# 08-Power.net
KiCad netlist of a schematic drawn in Altium Designer
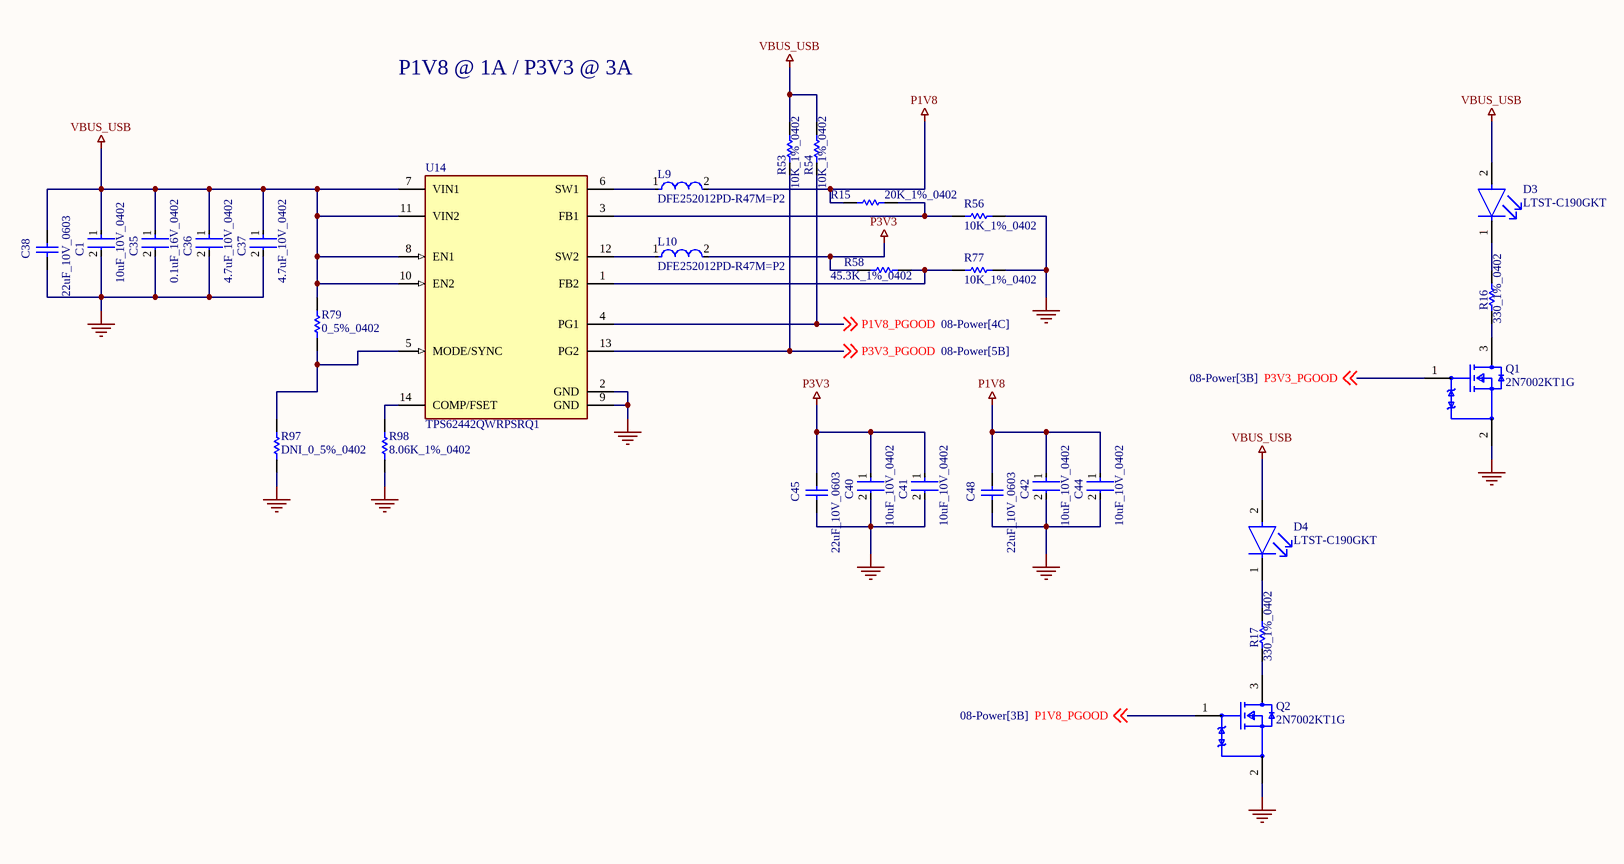
[diagram p0: 08-Power.SchDoc]

(export (version "E")
  (design (tool "Eeschema 10.0.6"))
  (components
    (comp (ref "C1")
      (value "10uF_10V_0402")
      (footprint "FP-CL05A106MP5NUNC-MFG")
      (description "CAP CER 10UF 10V X5R 0402")
      (fields
        (field (name "OCTOPART") "https://octopart.com/cl05a106mp5nunc-samsung-22457395")
        (field (name "TOLERANCE") "20%")
      )
      (libsource (lib "Altium Content Vault") (part "b4654b650e69147ec39a6b967a45e02"))
    )
    (comp (ref "C35")
      (value "0.1uF_16V_0402")
      (footprint "FP-C0402-BB-MFG")
      (description "CAP CER 0.1UF 16V 5% X7R 0402")
      (fields
        (field (name "MANUFACTURER") "Kemet")
        (field (name "MANUFACTURER PART NUMBER") "C0402C104J4RACTU")
      )
      (libsource (lib "Altium Content Vault") (part "b4654b650e69147ec39a6b967a45e02"))
    )
    (comp (ref "C36")
      (value "4.7uF_10V_0402")
      (footprint "FP-C1005-050-0_15-MFG")
      (description "CAP CER 4.7UF 10V X5R 0402")
      (fields (field (name "TOLERANCE") "10%"))
      (libsource (lib "Altium Content Vault") (part "b4654b650e69147ec39a6b967a45e02"))
    )
    (comp (ref "C37")
      (value "4.7uF_10V_0402")
      (footprint "FP-C1005-050-0_15-MFG")
      (description "CAP CER 4.7UF 10V X5R 0402")
      (fields (field (name "TOLERANCE") "10%"))
      (libsource (lib "Altium Content Vault") (part "b4654b650e69147ec39a6b967a45e02"))
    )
    (comp (ref "C38")
      (value "22uF_10V_0603")
      (footprint "CAPC1608X100X20ML10")
      (description "Chip Capacitor, 22 uF, +/- 20%, 10 V, -55 to 85 degC, 0603 (1608 Metric), RoHS, Tape and Reel")
      (fields (field (name "MANUFACTURER") "TDK") (field (name "TOLERANCE") "±20%"))
      (libsource (lib "Altium Content Vault") (part "CAP-NP-2"))
    )
    (comp (ref "C40")
      (value "10uF_10V_0402")
      (footprint "FP-CL05A106MP5NUNC-MFG")
      (description "CAP CER 10UF 10V X5R 0402")
      (fields
        (field (name "OCTOPART") "https://octopart.com/cl05a106mp5nunc-samsung-22457395")
        (field (name "TOLERANCE") "20%")
      )
      (libsource (lib "Altium Content Vault") (part "b4654b650e69147ec39a6b967a45e02"))
    )
    (comp (ref "C41")
      (value "10uF_10V_0402")
      (footprint "FP-CL05A106MP5NUNC-MFG")
      (description "CAP CER 10UF 10V X5R 0402")
      (fields
        (field (name "OCTOPART") "https://octopart.com/cl05a106mp5nunc-samsung-22457395")
        (field (name "TOLERANCE") "20%")
      )
      (libsource (lib "Altium Content Vault") (part "b4654b650e69147ec39a6b967a45e02"))
    )
    (comp (ref "C42")
      (value "10uF_10V_0402")
      (footprint "FP-CL05A106MP5NUNC-MFG")
      (description "CAP CER 10UF 10V X5R 0402")
      (fields
        (field (name "OCTOPART") "https://octopart.com/cl05a106mp5nunc-samsung-22457395")
        (field (name "TOLERANCE") "20%")
      )
      (libsource (lib "Altium Content Vault") (part "b4654b650e69147ec39a6b967a45e02"))
    )
    (comp (ref "C44")
      (value "10uF_10V_0402")
      (footprint "FP-CL05A106MP5NUNC-MFG")
      (description "CAP CER 10UF 10V X5R 0402")
      (fields
        (field (name "OCTOPART") "https://octopart.com/cl05a106mp5nunc-samsung-22457395")
        (field (name "TOLERANCE") "20%")
      )
      (libsource (lib "Altium Content Vault") (part "b4654b650e69147ec39a6b967a45e02"))
    )
    (comp (ref "C45")
      (value "22uF_10V_0603")
      (footprint "CAPC1608X100X20ML10")
      (description "Chip Capacitor, 22 uF, +/- 20%, 10 V, -55 to 85 degC, 0603 (1608 Metric), RoHS, Tape and Reel")
      (fields (field (name "MANUFACTURER") "TDK") (field (name "TOLERANCE") "±20%"))
      (libsource (lib "Altium Content Vault") (part "CAP-NP-2"))
    )
    (comp (ref "C48")
      (value "22uF_10V_0603")
      (footprint "CAPC1608X100X20ML10")
      (description "Chip Capacitor, 22 uF, +/- 20%, 10 V, -55 to 85 degC, 0603 (1608 Metric), RoHS, Tape and Reel")
      (fields (field (name "MANUFACTURER") "TDK") (field (name "TOLERANCE") "±20%"))
      (libsource (lib "Altium Content Vault") (part "CAP-NP-2"))
    )
    (comp (ref "D3")
      (value "LTST-C190GKT")
      (footprint "FP-LTST-C190GKT-MFG")
      (description "LED GREEN CLEAR CHIP SMD")
      (fields (field (name "VOLTAGE") "2V"))
      (libsource (lib "Altium Content Vault") (part "8706943c75ba83719d021d2fdc84c58"))
    )
    (comp (ref "D4")
      (value "LTST-C190GKT")
      (footprint "FP-LTST-C190GKT-MFG")
      (description "LED GREEN CLEAR CHIP SMD")
      (fields (field (name "VOLTAGE") "2V"))
      (libsource (lib "Altium Content Vault") (part "8706943c75ba83719d021d2fdc84c58"))
    )
    (comp (ref "L9")
      (value "DFE252012PD-R47M=P2")
      (footprint "FP-DFE252012C-IPC_A")
      (description "Shielded Wirewound Inductor 0.47uH 20% 4000mA 0.027Ω 1008 (2520)")
      (libsource (lib "Altium Content Vault") (part "725321dda6339637d4d059423bc1c3c"))
    )
    (comp (ref "L10")
      (value "DFE252012PD-R47M=P2")
      (footprint "FP-DFE252012C-IPC_A")
      (description "Shielded Wirewound Inductor 0.47uH 20% 4000mA 0.027Ω 1008 (2520)")
      (libsource (lib "Altium Content Vault") (part "725321dda6339637d4d059423bc1c3c"))
    )
    (comp (ref "Q1")
      (value "2N7002KT1G")
      (footprint "FP-318-08-MFG")
      (description "MOSFET N-CH 60V 320MA SOT-23")
      (libsource (lib "Altium Content Vault") (part "3e4cd9f5cc51be7b9a7c969a1e66e82"))
    )
    (comp (ref "Q2")
      (value "2N7002KT1G")
      (footprint "FP-318-08-MFG")
      (description "MOSFET N-CH 60V 320MA SOT-23")
      (libsource (lib "Altium Content Vault") (part "3e4cd9f5cc51be7b9a7c969a1e66e82"))
    )
    (comp (ref "R15")
      (value "20K_1%_0402")
      (footprint "RESC1005X40X25ML10T10")
      (fields
        (field (name "MANUFACTURER") "TE Connectivity / AMP")
        (field (name "PART NUMBER") "CRG0402F20K")
      )
      (libsource (lib "Altium Content Vault") (part "RES"))
    )
    (comp (ref "R16")
      (value "330_1%_0402")
      (footprint "RESC1005X40X25NL10T10")
      (fields (field (name "MANUFACTURER") "Panasonic") (field (name "PART NUMBER") "ERA-2AED331X"))
      (libsource (lib "Altium Content Vault") (part "RES"))
    )
    (comp (ref "R17")
      (value "330_1%_0402")
      (footprint "RESC1005X40X25NL10T10")
      (fields (field (name "MANUFACTURER") "Panasonic") (field (name "PART NUMBER") "ERA-2AED331X"))
      (libsource (lib "Altium Content Vault") (part "RES"))
    )
    (comp (ref "R53")
      (value "10K_1%_0402")
      (footprint "RESC1005X40X25NL10T10")
      (fields (field (name "MANUFACTURER") "Bourns") (field (name "PART NUMBER") "CR0402-FX-1002GLF"))
      (libsource (lib "Altium Content Vault") (part "RES"))
    )
    (comp (ref "R54")
      (value "10K_1%_0402")
      (footprint "RESC1005X40X25NL10T10")
      (fields (field (name "MANUFACTURER") "Bourns") (field (name "PART NUMBER") "CR0402-FX-1002GLF"))
      (libsource (lib "Altium Content Vault") (part "RES"))
    )
    (comp (ref "R56")
      (value "10K_1%_0402")
      (footprint "RESC1005X40X25NL10T10")
      (fields (field (name "MANUFACTURER") "Bourns") (field (name "PART NUMBER") "CR0402-FX-1002GLF"))
      (libsource (lib "Altium Content Vault") (part "RES"))
    )
    (comp (ref "R58")
      (value "45.3K_1%_0402")
      (footprint "RESC0402(1005)_L")
      (description "45K3 0.063W 1% 0402 (1005 Metric)  SMD")
      (fields (field (name "TOLERANCE") "1 %") (field (name "POWER") "0.063 W"))
      (libsource (lib "Altium Content Vault") (part "RES"))
    )
    (comp (ref "R77")
      (value "10K_1%_0402")
      (footprint "RESC1005X40X25NL10T10")
      (fields (field (name "MANUFACTURER") "Bourns") (field (name "PART NUMBER") "CR0402-FX-1002GLF"))
      (libsource (lib "Altium Content Vault") (part "RES"))
    )
    (comp (ref "R79")
      (value "0_5%_0402")
      (footprint "RESC1005X40X25NL05T10")
      (fields (field (name "MANUFACTURER") "Panasonic") (field (name "PART NUMBER") "ERJ-U020R00X"))
      (libsource (lib "Altium Content Vault") (part "RES"))
    )
    (comp (ref "R97")
      (value "DNI_0_5%_0402")
      (footprint "RESC1005X40X25NL05T10")
      (fields (field (name "MANUFACTURER") "Panasonic") (field (name "PART NUMBER") "ERJ-U020R00X"))
      (libsource (lib "Altium Content Vault") (part "RES"))
    )
    (comp (ref "R98")
      (value "8.06K_1%_0402")
      (footprint "RESC1005X40X25ML05T05")
      (description "Chip Resistor, 8.06 KOhm, +/- 1%, 63 mW, -55 to 155 degC, 0402 (1005 Metric), RoHS, Tape and Reel")
      (fields (field (name "PARTNUMBER") "CRCW04028K06FKED") (field (name "TOLERANCE") "1%"))
      (libsource (lib "Altium Content Vault") (part "RES-2"))
    )
    (comp (ref "U14")
      (value "TPS62442QWRPSRQ1")
      (footprint "FP-RQR0014A-MFG")
      (description "Adjustable-Frequency Dual Step-Down Converter, 2.7-6V VIN, 0.6-5.5V 2A VOUT, VQFN-HR14")
      (libsource (lib "Altium Content Vault") (part "72c5b9bb22caeb688b1070b758806aa"))
    )
  )
  (nets
    (net (code "1") (name "GND") (class "Default")
      (node (ref "C1") (pin "2") (pinfunction "2_2") (pintype "passive"))
      (node (ref "C35") (pin "2") (pinfunction "2_2") (pintype "passive"))
      (node (ref "C36") (pin "2") (pinfunction "2_2") (pintype "passive"))
      (node (ref "C37") (pin "2") (pinfunction "2_2") (pintype "passive"))
      (node (ref "C38") (pin "1") (pinfunction "1_1") (pintype "passive"))
      (node (ref "C40") (pin "2") (pinfunction "2_2") (pintype "passive"))
      (node (ref "C41") (pin "2") (pinfunction "2_2") (pintype "passive"))
      (node (ref "C42") (pin "2") (pinfunction "2_2") (pintype "passive"))
      (node (ref "C44") (pin "2") (pinfunction "2_2") (pintype "passive"))
      (node (ref "C45") (pin "1") (pinfunction "1_1") (pintype "passive"))
      (node (ref "C48") (pin "1") (pinfunction "1_1") (pintype "passive"))
      (node (ref "Q1") (pin "2") (pinfunction "Source_2") (pintype "passive"))
      (node (ref "Q2") (pin "2") (pinfunction "Source_2") (pintype "passive"))
      (node (ref "R56") (pin "1") (pinfunction "1_1") (pintype "passive"))
      (node (ref "R77") (pin "1") (pinfunction "1_1") (pintype "passive"))
      (node (ref "R97") (pin "1") (pinfunction "1_1") (pintype "passive"))
      (node (ref "R98") (pin "1") (pinfunction "1_1") (pintype "passive"))
      (node (ref "U14") (pin "2") (pinfunction "GND_2") (pintype "power_in"))
      (node (ref "U14") (pin "9") (pinfunction "GND_9") (pintype "power_in"))
    )
    (net (code "2") (name "Net-(D3-C)") (class "Default")
      (node (ref "D3") (pin "1") (pinfunction "C_1") (pintype "passive"))
      (node (ref "R16") (pin "2") (pinfunction "2_2") (pintype "passive"))
    )
    (net (code "3") (name "Net-(D4-C)") (class "Default")
      (node (ref "D4") (pin "1") (pinfunction "C_1") (pintype "passive"))
      (node (ref "R17") (pin "2") (pinfunction "2_2") (pintype "passive"))
    )
    (net (code "4") (name "Net-(Q1-Drain)") (class "Default")
      (node (ref "Q1") (pin "3") (pinfunction "Drain_3") (pintype "passive"))
      (node (ref "R16") (pin "1") (pinfunction "1_1") (pintype "passive"))
    )
    (net (code "5") (name "Net-(Q2-Drain)") (class "Default")
      (node (ref "Q2") (pin "3") (pinfunction "Drain_3") (pintype "passive"))
      (node (ref "R17") (pin "1") (pinfunction "1_1") (pintype "passive"))
    )
    (net (code "6") (name "Net-(U14-COMP{slash}FSET)") (class "Default")
      (node (ref "R98") (pin "2") (pinfunction "2_2") (pintype "passive"))
      (node (ref "U14") (pin "14") (pinfunction "COMP/FSET_14") (pintype "passive"))
    )
    (net (code "7") (name "Net-(U14-FB1)") (class "Default")
      (node (ref "R15") (pin "2") (pinfunction "2_2") (pintype "passive"))
      (node (ref "R56") (pin "2") (pinfunction "2_2") (pintype "passive"))
      (node (ref "U14") (pin "3") (pinfunction "FB1_3") (pintype "passive"))
    )
    (net (code "8") (name "Net-(U14-FB2)") (class "Default")
      (node (ref "R58") (pin "2") (pinfunction "2_2") (pintype "passive"))
      (node (ref "R77") (pin "2") (pinfunction "2_2") (pintype "passive"))
      (node (ref "U14") (pin "1") (pinfunction "FB2_1") (pintype "passive"))
    )
    (net (code "9") (name "Net-(U14-MODE{slash}SYNC)") (class "Default")
      (node (ref "R79") (pin "1") (pinfunction "1_1") (pintype "passive"))
      (node (ref "R97") (pin "2") (pinfunction "2_2") (pintype "passive"))
      (node (ref "U14") (pin "5") (pinfunction "MODE/SYNC_5") (pintype "input"))
    )
    (net (code "10") (name "Net-(U14-SW1)") (class "Default")
      (node (ref "L9") (pin "1") (pinfunction "1_1") (pintype "passive"))
      (node (ref "U14") (pin "6") (pinfunction "SW1_6") (pintype "passive"))
    )
    (net (code "11") (name "Net-(U14-SW2)") (class "Default")
      (node (ref "L10") (pin "1") (pinfunction "1_1") (pintype "passive"))
      (node (ref "U14") (pin "12") (pinfunction "SW2_12") (pintype "passive"))
    )
    (net (code "12") (name "P1V8") (class "Default")
      (node (ref "C42") (pin "1") (pinfunction "1_1") (pintype "passive"))
      (node (ref "C44") (pin "1") (pinfunction "1_1") (pintype "passive"))
      (node (ref "C48") (pin "2") (pinfunction "2_2") (pintype "passive"))
      (node (ref "L9") (pin "2") (pinfunction "2_2") (pintype "passive"))
      (node (ref "R15") (pin "1") (pinfunction "1_1") (pintype "passive"))
    )
    (net (code "13") (name "P1V8_PGOOD") (class "Default")
      (node (ref "Q2") (pin "1") (pinfunction "Gate_1") (pintype "passive"))
      (node (ref "R54") (pin "1") (pinfunction "1_1") (pintype "passive"))
      (node (ref "U14") (pin "4") (pinfunction "PG1_4") (pintype "open_collector"))
    )
    (net (code "14") (name "P3V3") (class "Default")
      (node (ref "C40") (pin "1") (pinfunction "1_1") (pintype "passive"))
      (node (ref "C41") (pin "1") (pinfunction "1_1") (pintype "passive"))
      (node (ref "C45") (pin "2") (pinfunction "2_2") (pintype "passive"))
      (node (ref "L10") (pin "2") (pinfunction "2_2") (pintype "passive"))
      (node (ref "R58") (pin "1") (pinfunction "1_1") (pintype "passive"))
    )
    (net (code "15") (name "P3V3_PGOOD") (class "Default")
      (node (ref "Q1") (pin "1") (pinfunction "Gate_1") (pintype "passive"))
      (node (ref "R53") (pin "1") (pinfunction "1_1") (pintype "passive"))
      (node (ref "U14") (pin "13") (pinfunction "PG2_13") (pintype "open_collector"))
    )
    (net (code "16") (name "VBUS_USB") (class "Default")
      (node (ref "C1") (pin "1") (pinfunction "1_1") (pintype "passive"))
      (node (ref "C35") (pin "1") (pinfunction "1_1") (pintype "passive"))
      (node (ref "C36") (pin "1") (pinfunction "1_1") (pintype "passive"))
      (node (ref "C37") (pin "1") (pinfunction "1_1") (pintype "passive"))
      (node (ref "C38") (pin "2") (pinfunction "2_2") (pintype "passive"))
      (node (ref "D3") (pin "2") (pinfunction "A_2") (pintype "passive"))
      (node (ref "D4") (pin "2") (pinfunction "A_2") (pintype "passive"))
      (node (ref "R53") (pin "2") (pinfunction "2_2") (pintype "passive"))
      (node (ref "R54") (pin "2") (pinfunction "2_2") (pintype "passive"))
      (node (ref "R79") (pin "2") (pinfunction "2_2") (pintype "passive"))
      (node (ref "U14") (pin "10") (pinfunction "EN2_10") (pintype "input"))
      (node (ref "U14") (pin "11") (pinfunction "VIN2_11") (pintype "power_in"))
      (node (ref "U14") (pin "7") (pinfunction "VIN1_7") (pintype "power_in"))
      (node (ref "U14") (pin "8") (pinfunction "EN1_8") (pintype "input"))
    )
  )
)
